# detektor_daging_celelng.net
KiCad netlist of a schematic drawn in EAGLE
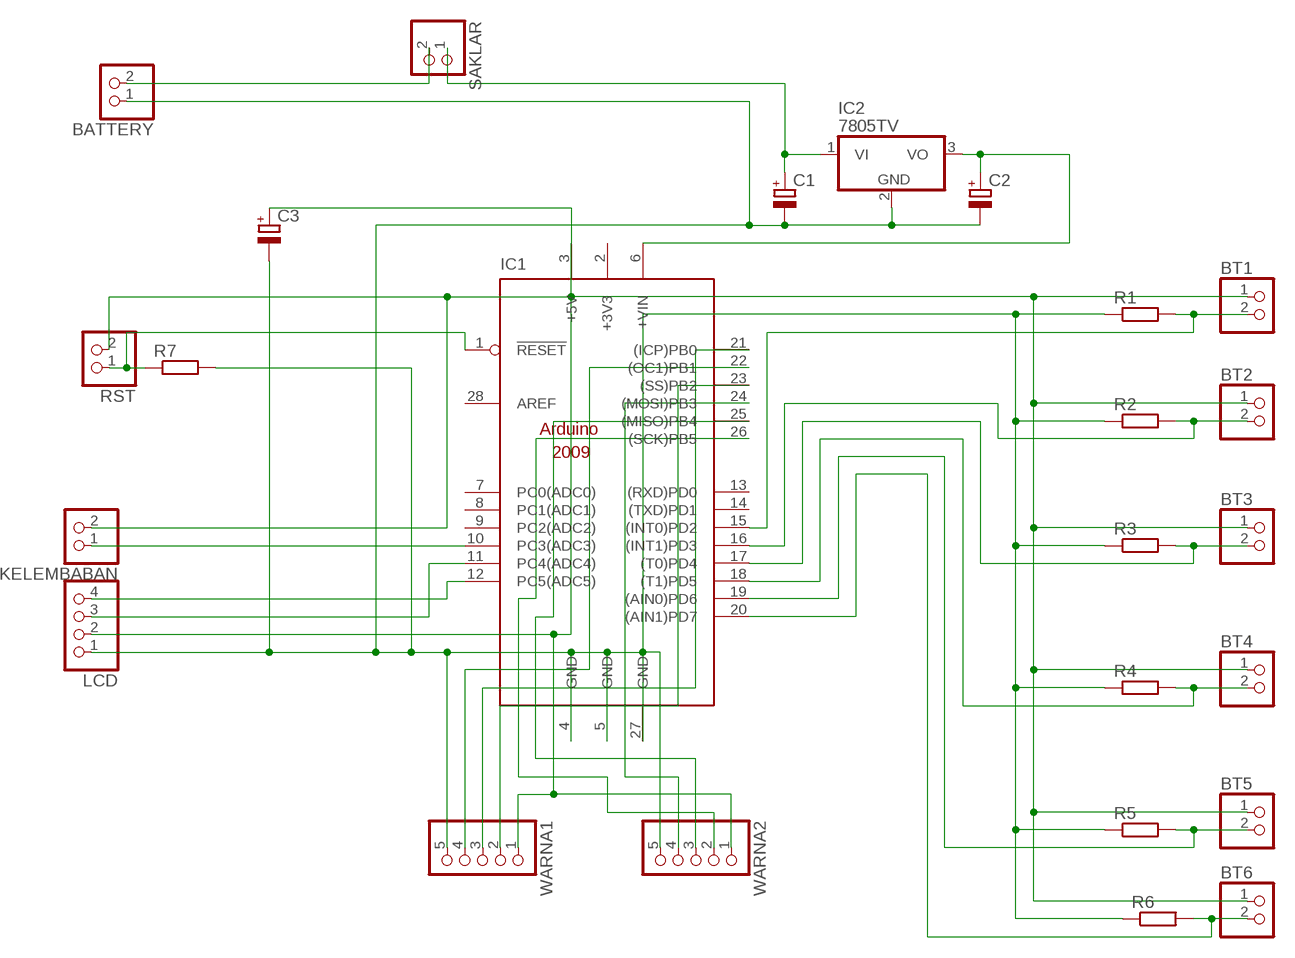
[diagram p0: schematic, sheet 1]

(export (version "E")
  (design (tool "Eeschema 10.0.6"))
  (components
    (comp (ref "BATTERY")
      (value "PINHD-1X2")
      (footprint "eagle-import:1X02")
      (libsource (lib "eagle-import") (part "PINHD-1X2"))
    )
    (comp (ref "BT1")
      (value "PINHD-1X2")
      (footprint "eagle-import:1X02")
      (libsource (lib "eagle-import") (part "PINHD-1X2"))
    )
    (comp (ref "BT2")
      (value "PINHD-1X2")
      (footprint "eagle-import:1X02")
      (libsource (lib "eagle-import") (part "PINHD-1X2"))
    )
    (comp (ref "BT3")
      (value "PINHD-1X2")
      (footprint "eagle-import:1X02")
      (libsource (lib "eagle-import") (part "PINHD-1X2"))
    )
    (comp (ref "BT4")
      (value "PINHD-1X2")
      (footprint "eagle-import:1X02")
      (libsource (lib "eagle-import") (part "PINHD-1X2"))
    )
    (comp (ref "BT5")
      (value "PINHD-1X2")
      (footprint "eagle-import:1X02")
      (libsource (lib "eagle-import") (part "PINHD-1X2"))
    )
    (comp (ref "BT6")
      (value "PINHD-1X2")
      (footprint "eagle-import:1X02")
      (libsource (lib "eagle-import") (part "PINHD-1X2"))
    )
    (comp (ref "C1")
      (value "CPOL-EUE2.5-7")
      (footprint "eagle-import:E2,5-7")
      (libsource (lib "eagle-import") (part "CPOL-EUE2.5-7"))
    )
    (comp (ref "C2")
      (value "CPOL-EUE2.5-7")
      (footprint "eagle-import:E2,5-7")
      (libsource (lib "eagle-import") (part "CPOL-EUE2.5-7"))
    )
    (comp (ref "C3")
      (value "CPOL-EUE2.5-7")
      (footprint "eagle-import:E2,5-7")
      (libsource (lib "eagle-import") (part "CPOL-EUE2.5-7"))
    )
    (comp (ref "IC1")
      (value "ARDUINO2009_PIN_10")
      (footprint "eagle-import:ARDUINO2009")
      (libsource (lib "eagle-import") (part "ARDUINO2009_PIN_10"))
    )
    (comp (ref "IC2")
      (value "7805TV")
      (footprint "eagle-import:TO220V")
      (libsource (lib "eagle-import") (part "78TV05"))
    )
    (comp (ref "KELEMBABAN")
      (value "PINHD-1X2")
      (footprint "eagle-import:1X02")
      (libsource (lib "eagle-import") (part "PINHD-1X2"))
    )
    (comp (ref "LCD")
      (value "PINHD-1X4")
      (footprint "eagle-import:1X04")
      (libsource (lib "eagle-import") (part "PINHD-1X4"))
    )
    (comp (ref "R1")
      (value "R-EU_0207/10")
      (footprint "eagle-import:0207_10")
      (libsource (lib "eagle-import") (part "R-EU_0207/10"))
    )
    (comp (ref "R2")
      (value "R-EU_0207/10")
      (footprint "eagle-import:0207_10")
      (libsource (lib "eagle-import") (part "R-EU_0207/10"))
    )
    (comp (ref "R3")
      (value "R-EU_0207/10")
      (footprint "eagle-import:0207_10")
      (libsource (lib "eagle-import") (part "R-EU_0207/10"))
    )
    (comp (ref "R4")
      (value "R-EU_0207/10")
      (footprint "eagle-import:0207_10")
      (libsource (lib "eagle-import") (part "R-EU_0207/10"))
    )
    (comp (ref "R5")
      (value "R-EU_0207/10")
      (footprint "eagle-import:0207_10")
      (libsource (lib "eagle-import") (part "R-EU_0207/10"))
    )
    (comp (ref "R6")
      (value "R-EU_0207/10")
      (footprint "eagle-import:0207_10")
      (libsource (lib "eagle-import") (part "R-EU_0207/10"))
    )
    (comp (ref "R7")
      (value "R-EU_0207/10")
      (footprint "eagle-import:0207_10")
      (libsource (lib "eagle-import") (part "R-EU_0207/10"))
    )
    (comp (ref "RST")
      (value "PINHD-1X2")
      (footprint "eagle-import:1X02")
      (libsource (lib "eagle-import") (part "PINHD-1X2"))
    )
    (comp (ref "SAKLAR")
      (value "PINHD-1X2")
      (footprint "eagle-import:1X02")
      (libsource (lib "eagle-import") (part "PINHD-1X2"))
    )
    (comp (ref "WARNA1")
      (value "PINHD-1X5")
      (footprint "eagle-import:1X05")
      (libsource (lib "eagle-import") (part "PINHD-1X5"))
    )
    (comp (ref "WARNA2")
      (value "PINHD-1X5")
      (footprint "eagle-import:1X05")
      (libsource (lib "eagle-import") (part "PINHD-1X5"))
    )
  )
  (nets
    (net (code "1") (name "/+3V3") (class "Default")
      (node (ref "IC1") (pin "2") (pinfunction "+3V3_2") (pintype "power_in"))
    )
    (net (code "2") (name "Net-(BATTERY-Pad2)") (class "Default")
      (node (ref "BATTERY") (pin "2") (pinfunction "2_2") (pintype "passive"))
      (node (ref "SAKLAR") (pin "2") (pinfunction "2_2") (pintype "passive"))
    )
    (net (code "3") (name "Net-(IC1-(AIN0)PD6)") (class "Default")
      (node (ref "BT5") (pin "2") (pinfunction "2_2") (pintype "passive"))
      (node (ref "IC1") (pin "19") (pinfunction "(AIN0)PD6_19") (pintype "bidirectional"))
      (node (ref "R5") (pin "2") (pinfunction "2_2") (pintype "passive"))
    )
    (net (code "4") (name "Net-(IC1-(AIN1)PD7)") (class "Default")
      (node (ref "BT6") (pin "2") (pinfunction "2_2") (pintype "passive"))
      (node (ref "IC1") (pin "20") (pinfunction "(AIN1)PD7_20") (pintype "bidirectional"))
      (node (ref "R6") (pin "2") (pinfunction "2_2") (pintype "passive"))
    )
    (net (code "5") (name "Net-(IC1-(ICP)PB0)") (class "Default")
      (node (ref "IC1") (pin "21") (pinfunction "(ICP)PB0_21") (pintype "bidirectional"))
      (node (ref "WARNA1") (pin "3") (pinfunction "3_3") (pintype "passive"))
    )
    (net (code "6") (name "Net-(IC1-(INT0)PD2)") (class "Default")
      (node (ref "BT1") (pin "2") (pinfunction "2_2") (pintype "passive"))
      (node (ref "IC1") (pin "15") (pinfunction "(INT0)PD2_15") (pintype "bidirectional"))
      (node (ref "R1") (pin "2") (pinfunction "2_2") (pintype "passive"))
    )
    (net (code "7") (name "Net-(IC1-(INT1)PD3)") (class "Default")
      (node (ref "BT2") (pin "2") (pinfunction "2_2") (pintype "passive"))
      (node (ref "IC1") (pin "16") (pinfunction "(INT1)PD3_16") (pintype "bidirectional"))
      (node (ref "R2") (pin "2") (pinfunction "2_2") (pintype "passive"))
    )
    (net (code "8") (name "Net-(IC1-(MISO)PB4)") (class "Default")
      (node (ref "IC1") (pin "25") (pinfunction "(MISO)PB4_25") (pintype "bidirectional"))
      (node (ref "WARNA2") (pin "3") (pinfunction "3_3") (pintype "passive"))
    )
    (net (code "9") (name "Net-(IC1-(MOSI)PB3)") (class "Default")
      (node (ref "IC1") (pin "24") (pinfunction "(MOSI)PB3_24") (pintype "bidirectional"))
      (node (ref "WARNA2") (pin "4") (pinfunction "4_4") (pintype "passive"))
    )
    (net (code "10") (name "Net-(IC1-(OC1)PB1)") (class "Default")
      (node (ref "IC1") (pin "22") (pinfunction "(OC1)PB1_22") (pintype "bidirectional"))
      (node (ref "WARNA1") (pin "4") (pinfunction "4_4") (pintype "passive"))
    )
    (net (code "11") (name "Net-(IC1-(SCK)PB5)") (class "Default")
      (node (ref "IC1") (pin "26") (pinfunction "(SCK)PB5_26") (pintype "bidirectional"))
      (node (ref "WARNA2") (pin "2") (pinfunction "2_2") (pintype "passive"))
    )
    (net (code "12") (name "Net-(IC1-(SS)PB2)") (class "Default")
      (node (ref "IC1") (pin "23") (pinfunction "(SS)PB2_23") (pintype "bidirectional"))
      (node (ref "WARNA1") (pin "2") (pinfunction "2_2") (pintype "passive"))
    )
    (net (code "13") (name "Net-(IC1-(T0)PD4)") (class "Default")
      (node (ref "BT3") (pin "2") (pinfunction "2_2") (pintype "passive"))
      (node (ref "IC1") (pin "17") (pinfunction "(T0)PD4_17") (pintype "bidirectional"))
      (node (ref "R3") (pin "2") (pinfunction "2_2") (pintype "passive"))
    )
    (net (code "14") (name "Net-(IC1-(T1)PD5)") (class "Default")
      (node (ref "BT4") (pin "2") (pinfunction "2_2") (pintype "passive"))
      (node (ref "IC1") (pin "18") (pinfunction "(T1)PD5_18") (pintype "bidirectional"))
      (node (ref "R4") (pin "2") (pinfunction "2_2") (pintype "passive"))
    )
    (net (code "15") (name "Net-(IC1-+5V)") (class "Default")
      (node (ref "BT1") (pin "1") (pinfunction "1_1") (pintype "passive"))
      (node (ref "BT2") (pin "1") (pinfunction "1_1") (pintype "passive"))
      (node (ref "BT3") (pin "1") (pinfunction "1_1") (pintype "passive"))
      (node (ref "BT4") (pin "1") (pinfunction "1_1") (pintype "passive"))
      (node (ref "BT5") (pin "1") (pinfunction "1_1") (pintype "passive"))
      (node (ref "BT6") (pin "1") (pinfunction "1_1") (pintype "passive"))
      (node (ref "C3") (pin "+") (pinfunction "+_+") (pintype "passive"))
      (node (ref "IC1") (pin "3") (pinfunction "+5V_3") (pintype "power_in"))
      (node (ref "KELEMBABAN") (pin "2") (pinfunction "2_2") (pintype "passive"))
      (node (ref "LCD") (pin "2") (pinfunction "2_2") (pintype "passive"))
      (node (ref "RST") (pin "2") (pinfunction "2_2") (pintype "passive"))
      (node (ref "WARNA1") (pin "1") (pinfunction "1_1") (pintype "passive"))
      (node (ref "WARNA2") (pin "1") (pinfunction "1_1") (pintype "passive"))
    )
    (net (code "16") (name "Net-(IC1-+VIN)") (class "Default")
      (node (ref "C2") (pin "+") (pinfunction "+_+") (pintype "passive"))
      (node (ref "IC1") (pin "6") (pinfunction "+VIN_6") (pintype "bidirectional"))
      (node (ref "IC2") (pin "3") (pinfunction "VO_3") (pintype "passive"))
    )
    (net (code "17") (name "Net-(IC1-PC3(ADC3))") (class "Default")
      (node (ref "IC1") (pin "10") (pinfunction "PC3(ADC3)_10") (pintype "bidirectional"))
      (node (ref "KELEMBABAN") (pin "1") (pinfunction "1_1") (pintype "passive"))
    )
    (net (code "18") (name "Net-(IC1-PC4(ADC4))") (class "Default")
      (node (ref "IC1") (pin "11") (pinfunction "PC4(ADC4)_11") (pintype "bidirectional"))
      (node (ref "LCD") (pin "3") (pinfunction "3_3") (pintype "passive"))
    )
    (net (code "19") (name "Net-(IC1-PC5(ADC5))") (class "Default")
      (node (ref "IC1") (pin "12") (pinfunction "PC5(ADC5)_12") (pintype "bidirectional"))
      (node (ref "LCD") (pin "4") (pinfunction "4_4") (pintype "passive"))
    )
    (net (code "20") (name "Net-(IC1-~{RESET})") (class "Default")
      (node (ref "IC1") (pin "1") (pinfunction "~{RESET}_1") (pintype "bidirectional"))
      (node (ref "R7") (pin "1") (pinfunction "1_1") (pintype "passive"))
      (node (ref "RST") (pin "1") (pinfunction "1_1") (pintype "passive"))
    )
    (net (code "21") (name "Net-(IC2-GND)") (class "Default")
      (node (ref "BATTERY") (pin "1") (pinfunction "1_1") (pintype "passive"))
      (node (ref "C1") (pin "-") (pinfunction "-_-") (pintype "passive"))
      (node (ref "C2") (pin "-") (pinfunction "-_-") (pintype "passive"))
      (node (ref "C3") (pin "-") (pinfunction "-_-") (pintype "passive"))
      (node (ref "IC1") (pin "27") (pinfunction "GND_27") (pintype "power_in"))
      (node (ref "IC1") (pin "4") (pinfunction "GND_4") (pintype "power_in"))
      (node (ref "IC1") (pin "5") (pinfunction "GND_5") (pintype "power_in"))
      (node (ref "IC2") (pin "2") (pinfunction "GND_2") (pintype "passive"))
      (node (ref "LCD") (pin "1") (pinfunction "1_1") (pintype "passive"))
      (node (ref "R1") (pin "1") (pinfunction "1_1") (pintype "passive"))
      (node (ref "R2") (pin "1") (pinfunction "1_1") (pintype "passive"))
      (node (ref "R3") (pin "1") (pinfunction "1_1") (pintype "passive"))
      (node (ref "R4") (pin "1") (pinfunction "1_1") (pintype "passive"))
      (node (ref "R5") (pin "1") (pinfunction "1_1") (pintype "passive"))
      (node (ref "R6") (pin "1") (pinfunction "1_1") (pintype "passive"))
      (node (ref "R7") (pin "2") (pinfunction "2_2") (pintype "passive"))
      (node (ref "WARNA1") (pin "5") (pinfunction "5_5") (pintype "passive"))
      (node (ref "WARNA2") (pin "5") (pinfunction "5_5") (pintype "passive"))
    )
    (net (code "22") (name "Net-(IC2-VI)") (class "Default")
      (node (ref "C1") (pin "+") (pinfunction "+_+") (pintype "passive"))
      (node (ref "IC2") (pin "1") (pinfunction "VI_1") (pintype "input"))
      (node (ref "SAKLAR") (pin "1") (pinfunction "1_1") (pintype "passive"))
    )
    (net (code "23") (name "unconnected-(IC1-(RXD)PD0-Pad13)") (class "Default")
      (node (ref "IC1") (pin "13") (pinfunction "(RXD)PD0_13") (pintype "bidirectional"))
    )
    (net (code "24") (name "unconnected-(IC1-(TXD)PD1-Pad14)") (class "Default")
      (node (ref "IC1") (pin "14") (pinfunction "(TXD)PD1_14") (pintype "bidirectional"))
    )
    (net (code "25") (name "unconnected-(IC1-AREF-Pad28)") (class "Default")
      (node (ref "IC1") (pin "28") (pinfunction "AREF_28") (pintype "bidirectional"))
    )
    (net (code "26") (name "unconnected-(IC1-PC0(ADC0)-Pad7)") (class "Default")
      (node (ref "IC1") (pin "7") (pinfunction "PC0(ADC0)_7") (pintype "bidirectional"))
    )
    (net (code "27") (name "unconnected-(IC1-PC1(ADC1)-Pad8)") (class "Default")
      (node (ref "IC1") (pin "8") (pinfunction "PC1(ADC1)_8") (pintype "bidirectional"))
    )
    (net (code "28") (name "unconnected-(IC1-PC2(ADC2)-Pad9)") (class "Default")
      (node (ref "IC1") (pin "9") (pinfunction "PC2(ADC2)_9") (pintype "bidirectional"))
    )
  )
)
